# Sheet2.net
KiCad netlist of a schematic drawn in Altium Designer
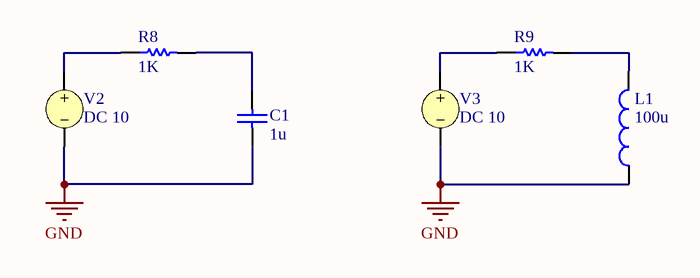
[diagram p0: Sheet2.SchDoc]

(export (version "E")
  (design (tool "Eeschema 10.0.6"))
  (components
    (comp (ref "C1")
      (value "1u")
      (description "Capacitor")
      (libsource (lib "Simulation Generic Components") (part "Capacitor"))
    )
    (comp (ref "L1")
      (value "100u")
      (description "Inductor")
      (libsource (lib "Simulation Generic Components") (part "Inductor"))
    )
    (comp (ref "R8")
      (value "1K")
      (description "Resistor")
      (libsource (lib "Simulation Generic Components") (part "Resistor"))
    )
    (comp (ref "R9")
      (value "1K")
      (description "Resistor")
      (libsource (lib "Simulation Generic Components") (part "Resistor"))
    )
    (comp (ref "V2")
      (value "DC 10")
      (description "Voltage Source")
      (fields (field (name "PUBLISHER") "Altium Limited"))
      (libsource (lib "Simulation Generic Components") (part "VSRC"))
    )
    (comp (ref "V3")
      (value "DC 10")
      (description "Voltage Source")
      (fields (field (name "PUBLISHER") "Altium Limited"))
      (libsource (lib "Simulation Generic Components") (part "VSRC"))
    )
  )
  (nets
    (net (code "1") (name "GND") (class "Default")
      (node (ref "C1") (pin "1") (pinfunction "1_1") (pintype "passive"))
      (node (ref "L1") (pin "1") (pinfunction "1_1") (pintype "passive"))
      (node (ref "V2") (pin "2") (pinfunction "2_2") (pintype "passive"))
      (node (ref "V3") (pin "2") (pinfunction "2_2") (pintype "passive"))
    )
    (net (code "2") (name "Net-(C1-Pad2)") (class "Default")
      (node (ref "C1") (pin "2") (pinfunction "2_2") (pintype "passive"))
      (node (ref "R8") (pin "2") (pinfunction "2_2") (pintype "passive"))
    )
    (net (code "3") (name "Net-(L1-Pad2)") (class "Default")
      (node (ref "L1") (pin "2") (pinfunction "2_2") (pintype "passive"))
      (node (ref "R9") (pin "2") (pinfunction "2_2") (pintype "passive"))
    )
    (net (code "4") (name "Net-(R8-Pad1)") (class "Default")
      (node (ref "R8") (pin "1") (pinfunction "1_1") (pintype "passive"))
      (node (ref "V2") (pin "1") (pinfunction "1_1") (pintype "passive"))
    )
    (net (code "5") (name "Net-(R9-Pad1)") (class "Default")
      (node (ref "R9") (pin "1") (pinfunction "1_1") (pintype "passive"))
      (node (ref "V3") (pin "1") (pinfunction "1_1") (pintype "passive"))
    )
  )
)
